# AS3364_waveform_VCA_0402_DIL_w_two_separ.net
KiCad netlist of a schematic drawn in EAGLE
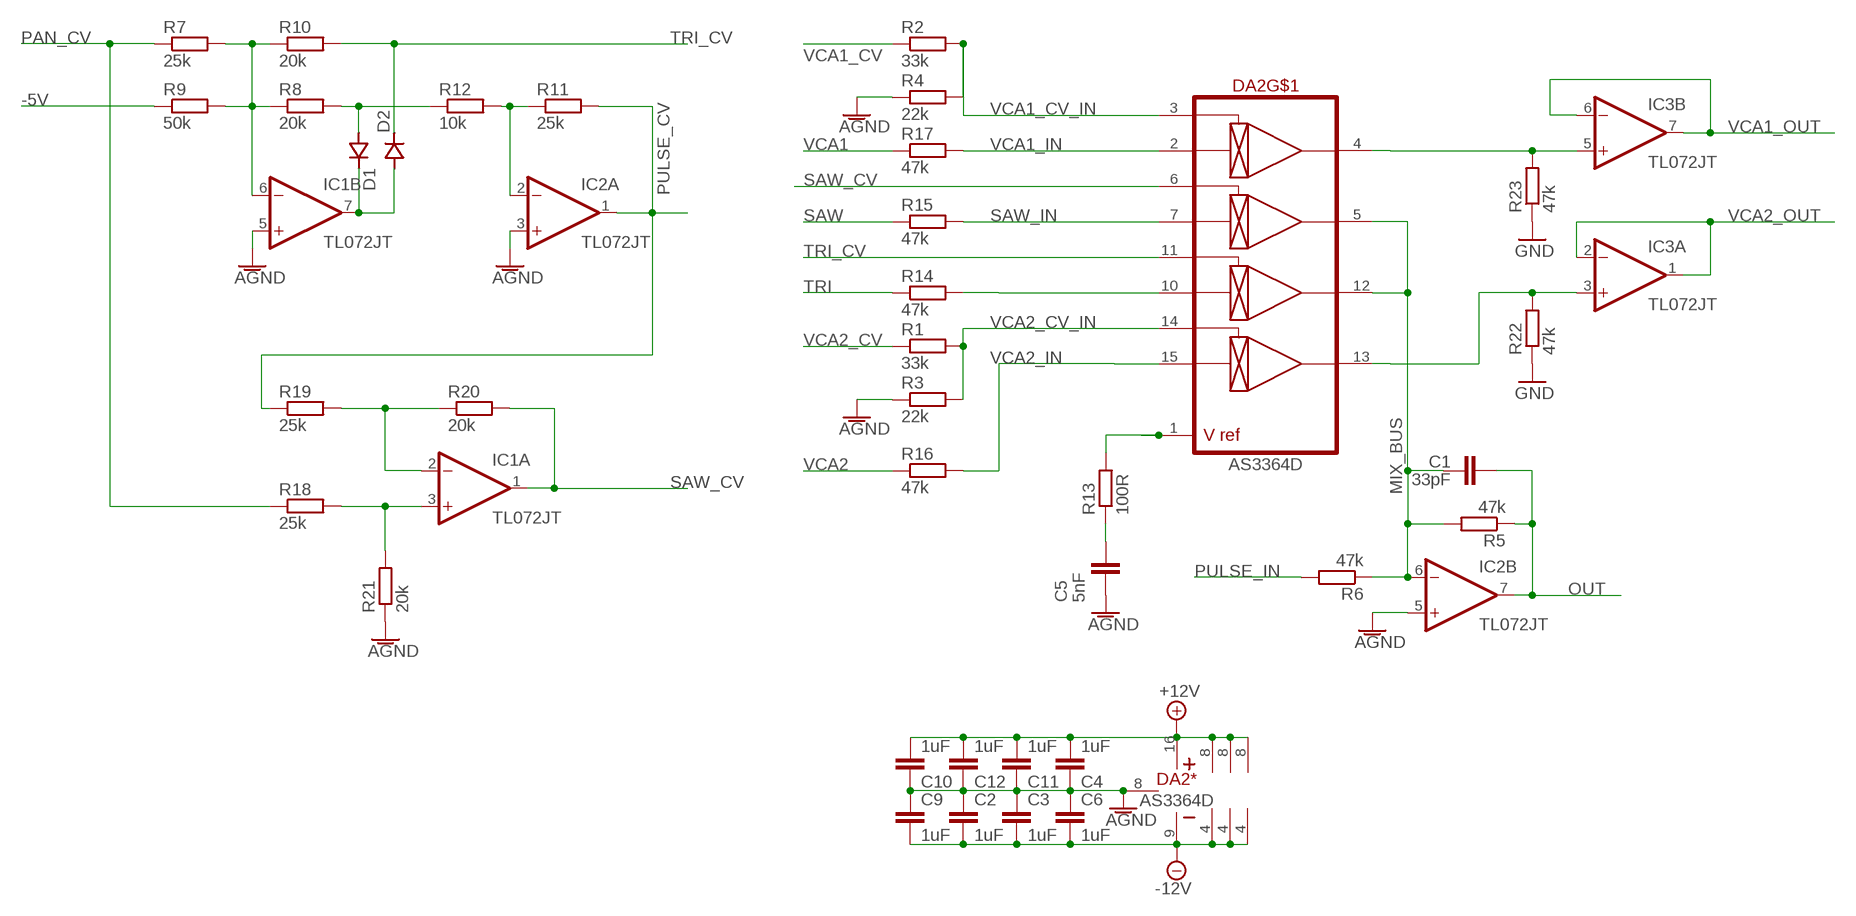
[diagram p0: schematic, sheet 1]

(export (version "E")
  (design (tool "Eeschema 10.0.6"))
  (components
    (comp (ref "C1")
      (value "33pF")
      (footprint "eagle-import:C0402-J")
      (libsource (lib "eagle-import") (part "C-EU-J"))
    )
    (comp (ref "C2")
      (value "1uF")
      (footprint "eagle-import:C0402-J")
      (libsource (lib "eagle-import") (part "C-EU-J"))
    )
    (comp (ref "C3")
      (value "1uF")
      (footprint "eagle-import:C0402-J")
      (libsource (lib "eagle-import") (part "C-EU-J"))
    )
    (comp (ref "C4")
      (value "1uF")
      (footprint "eagle-import:C0402-J")
      (libsource (lib "eagle-import") (part "C-EU-J"))
    )
    (comp (ref "C5")
      (value "5nF")
      (footprint "eagle-import:C0402-J")
      (libsource (lib "eagle-import") (part "C-EU-J"))
    )
    (comp (ref "C6")
      (value "1uF")
      (footprint "eagle-import:C0402-J")
      (libsource (lib "eagle-import") (part "C-EU-J"))
    )
    (comp (ref "C9")
      (value "1uF")
      (footprint "eagle-import:C0402-J")
      (libsource (lib "eagle-import") (part "C-EU-J"))
    )
    (comp (ref "C10")
      (value "1uF")
      (footprint "eagle-import:C0402-J")
      (libsource (lib "eagle-import") (part "C-EU-J"))
    )
    (comp (ref "C11")
      (value "1uF")
      (footprint "eagle-import:C0402-J")
      (libsource (lib "eagle-import") (part "C-EU-J"))
    )
    (comp (ref "C12")
      (value "1uF")
      (footprint "eagle-import:C0402-J")
      (libsource (lib "eagle-import") (part "C-EU-J"))
    )
    (comp (ref "D1")
      (value "DIODESOD323")
      (footprint "eagle-import:SOD323J")
      (fields (field (name "MPN") "CDSOD323-T05C"))
      (libsource (lib "eagle-import") (part "DIODESOD323"))
    )
    (comp (ref "D2")
      (value "DIODESOD323")
      (footprint "eagle-import:SOD323J")
      (fields (field (name "MPN") "CDSOD323-T05C"))
      (libsource (lib "eagle-import") (part "DIODESOD323"))
    )
    (comp (ref "DA2")
      (value "AS3364D")
      (footprint "eagle-import:DIL16J")
      (libsource (lib "eagle-import") (part "AS3364D"))
    )
    (comp (ref "IC1")
      (value "TL072JT")
      (footprint "eagle-import:TSSOP8J")
      (libsource (lib "eagle-import") (part "TL072JT"))
    )
    (comp (ref "IC2")
      (value "TL072JT")
      (footprint "eagle-import:TSSOP8J")
      (libsource (lib "eagle-import") (part "TL072JT"))
    )
    (comp (ref "IC3")
      (value "TL072JT")
      (footprint "eagle-import:TSSOP8J")
      (libsource (lib "eagle-import") (part "TL072JT"))
    )
    (comp (ref "R1")
      (value "33k")
      (footprint "eagle-import:R0402")
      (libsource (lib "eagle-import") (part "R-EU_R0402"))
    )
    (comp (ref "R2")
      (value "33k")
      (footprint "eagle-import:R0402")
      (libsource (lib "eagle-import") (part "R-EU_R0402"))
    )
    (comp (ref "R3")
      (value "22k")
      (footprint "eagle-import:R0402")
      (libsource (lib "eagle-import") (part "R-EU_R0402"))
    )
    (comp (ref "R4")
      (value "22k")
      (footprint "eagle-import:R0402")
      (libsource (lib "eagle-import") (part "R-EU_R0402"))
    )
    (comp (ref "R5")
      (value "47k")
      (footprint "eagle-import:R0402")
      (libsource (lib "eagle-import") (part "R-EU_R0402"))
    )
    (comp (ref "R6")
      (value "47k")
      (footprint "eagle-import:R0402")
      (libsource (lib "eagle-import") (part "R-EU_R0402"))
    )
    (comp (ref "R7")
      (value "25k")
      (footprint "eagle-import:R0402")
      (libsource (lib "eagle-import") (part "R-EU_R0402"))
    )
    (comp (ref "R8")
      (value "20k")
      (footprint "eagle-import:R0402")
      (libsource (lib "eagle-import") (part "R-EU_R0402"))
    )
    (comp (ref "R9")
      (value "50k")
      (footprint "eagle-import:R0402")
      (libsource (lib "eagle-import") (part "R-EU_R0402"))
    )
    (comp (ref "R10")
      (value "20k")
      (footprint "eagle-import:R0402")
      (libsource (lib "eagle-import") (part "R-EU_R0402"))
    )
    (comp (ref "R11")
      (value "25k")
      (footprint "eagle-import:R0402")
      (libsource (lib "eagle-import") (part "R-EU_R0402"))
    )
    (comp (ref "R12")
      (value "10k")
      (footprint "eagle-import:R0402")
      (libsource (lib "eagle-import") (part "R-EU_R0402"))
    )
    (comp (ref "R13")
      (value "100R")
      (footprint "eagle-import:R0402")
      (libsource (lib "eagle-import") (part "R-EU_R0402"))
    )
    (comp (ref "R14")
      (value "47k")
      (footprint "eagle-import:R0402")
      (libsource (lib "eagle-import") (part "R-EU_R0402"))
    )
    (comp (ref "R15")
      (value "47k")
      (footprint "eagle-import:R0402")
      (libsource (lib "eagle-import") (part "R-EU_R0402"))
    )
    (comp (ref "R16")
      (value "47k")
      (footprint "eagle-import:R0402")
      (libsource (lib "eagle-import") (part "R-EU_R0402"))
    )
    (comp (ref "R17")
      (value "47k")
      (footprint "eagle-import:R0402")
      (libsource (lib "eagle-import") (part "R-EU_R0402"))
    )
    (comp (ref "R18")
      (value "25k")
      (footprint "eagle-import:R0402")
      (libsource (lib "eagle-import") (part "R-EU_R0402"))
    )
    (comp (ref "R19")
      (value "25k")
      (footprint "eagle-import:R0402")
      (libsource (lib "eagle-import") (part "R-EU_R0402"))
    )
    (comp (ref "R20")
      (value "20k")
      (footprint "eagle-import:R0402")
      (libsource (lib "eagle-import") (part "R-EU_R0402"))
    )
    (comp (ref "R21")
      (value "20k")
      (footprint "eagle-import:R0402")
      (libsource (lib "eagle-import") (part "R-EU_R0402"))
    )
    (comp (ref "R22")
      (value "47k")
      (footprint "eagle-import:R0402")
      (libsource (lib "eagle-import") (part "R-EU_R0402"))
    )
    (comp (ref "R23")
      (value "47k")
      (footprint "eagle-import:R0402")
      (libsource (lib "eagle-import") (part "R-EU_R0402"))
    )
  )
  (nets
    (net (code "1") (name "+12V") (class "Default")
      (node (ref "C10") (pin "2") (pinfunction "2_2") (pintype "passive"))
      (node (ref "C11") (pin "2") (pinfunction "2_2") (pintype "passive"))
      (node (ref "C12") (pin "2") (pinfunction "2_2") (pintype "passive"))
      (node (ref "C4") (pin "2") (pinfunction "2_2") (pintype "passive"))
      (node (ref "DA2") (pin "16") (pinfunction "V+_16") (pintype "power_in"))
      (node (ref "IC1") (pin "8") (pinfunction "V+_8") (pintype "power_in"))
      (node (ref "IC2") (pin "8") (pinfunction "V+_8") (pintype "power_in"))
      (node (ref "IC3") (pin "8") (pinfunction "V+_8") (pintype "power_in"))
    )
    (net (code "2") (name "-12V") (class "Default")
      (node (ref "C2") (pin "1") (pinfunction "1_1") (pintype "passive"))
      (node (ref "C3") (pin "1") (pinfunction "1_1") (pintype "passive"))
      (node (ref "C6") (pin "1") (pinfunction "1_1") (pintype "passive"))
      (node (ref "C9") (pin "1") (pinfunction "1_1") (pintype "passive"))
      (node (ref "DA2") (pin "9") (pinfunction "V-_9") (pintype "power_in"))
      (node (ref "IC1") (pin "4") (pinfunction "V-_4") (pintype "power_in"))
      (node (ref "IC2") (pin "4") (pinfunction "V-_4") (pintype "power_in"))
      (node (ref "IC3") (pin "4") (pinfunction "V-_4") (pintype "power_in"))
    )
    (net (code "3") (name "/-5V") (class "Default")
      (node (ref "R9") (pin "1") (pinfunction "1_1") (pintype "passive"))
    )
    (net (code "4") (name "/MIX_BUS") (class "Default")
      (node (ref "C1") (pin "2") (pinfunction "2_2") (pintype "passive"))
      (node (ref "DA2") (pin "12") (pinfunction "OUT3_12") (pintype "output"))
      (node (ref "DA2") (pin "5") (pinfunction "OUT2_5") (pintype "output"))
      (node (ref "IC2") (pin "6") (pinfunction "-IN_6") (pintype "input"))
      (node (ref "R5") (pin "2") (pinfunction "2_2") (pintype "passive"))
      (node (ref "R6") (pin "1") (pinfunction "1_1") (pintype "passive"))
    )
    (net (code "5") (name "/OUT") (class "Default")
      (node (ref "C1") (pin "1") (pinfunction "1_1") (pintype "passive"))
      (node (ref "IC2") (pin "7") (pinfunction "OUT_7") (pintype "output"))
      (node (ref "R5") (pin "1") (pinfunction "1_1") (pintype "passive"))
    )
    (net (code "6") (name "/PAN_CV") (class "Default")
      (node (ref "R18") (pin "1") (pinfunction "1_1") (pintype "passive"))
      (node (ref "R7") (pin "1") (pinfunction "1_1") (pintype "passive"))
    )
    (net (code "7") (name "/PULSE_CV") (class "Default")
      (node (ref "IC2") (pin "1") (pinfunction "OUT_1") (pintype "output"))
      (node (ref "R11") (pin "2") (pinfunction "2_2") (pintype "passive"))
      (node (ref "R19") (pin "1") (pinfunction "1_1") (pintype "passive"))
    )
    (net (code "8") (name "/PULSE_IN") (class "Default")
      (node (ref "R6") (pin "2") (pinfunction "2_2") (pintype "passive"))
    )
    (net (code "9") (name "/SAW") (class "Default")
      (node (ref "R15") (pin "1") (pinfunction "1_1") (pintype "passive"))
    )
    (net (code "10") (name "/SAW_CV") (class "Default")
      (node (ref "DA2") (pin "6") (pinfunction "CV2_6") (pintype "input"))
      (node (ref "IC1") (pin "1") (pinfunction "OUT_1") (pintype "output"))
      (node (ref "R20") (pin "2") (pinfunction "2_2") (pintype "passive"))
    )
    (net (code "11") (name "/SAW_IN") (class "Default")
      (node (ref "DA2") (pin "7") (pinfunction "IN2_7") (pintype "input"))
      (node (ref "R15") (pin "2") (pinfunction "2_2") (pintype "passive"))
    )
    (net (code "12") (name "/TRI") (class "Default")
      (node (ref "R14") (pin "1") (pinfunction "1_1") (pintype "passive"))
    )
    (net (code "13") (name "/TRI_CV") (class "Default")
      (node (ref "D2") (pin "1") (pinfunction "C_1") (pintype "passive"))
      (node (ref "DA2") (pin "11") (pinfunction "CV3_11") (pintype "input"))
      (node (ref "R10") (pin "2") (pinfunction "2_2") (pintype "passive"))
    )
    (net (code "14") (name "/VCA1") (class "Default")
      (node (ref "R17") (pin "1") (pinfunction "1_1") (pintype "passive"))
    )
    (net (code "15") (name "/VCA1_CV") (class "Default")
      (node (ref "R2") (pin "1") (pinfunction "1_1") (pintype "passive"))
    )
    (net (code "16") (name "/VCA1_CV_IN") (class "Default")
      (node (ref "DA2") (pin "3") (pinfunction "CV1_3") (pintype "input"))
      (node (ref "R2") (pin "2") (pinfunction "2_2") (pintype "passive"))
      (node (ref "R4") (pin "2") (pinfunction "2_2") (pintype "passive"))
    )
    (net (code "17") (name "/VCA1_IN") (class "Default")
      (node (ref "DA2") (pin "2") (pinfunction "IN1_2") (pintype "input"))
      (node (ref "R17") (pin "2") (pinfunction "2_2") (pintype "passive"))
    )
    (net (code "18") (name "/VCA1_OUT") (class "Default")
      (node (ref "IC3") (pin "6") (pinfunction "-IN_6") (pintype "input"))
      (node (ref "IC3") (pin "7") (pinfunction "OUT_7") (pintype "output"))
    )
    (net (code "19") (name "/VCA2") (class "Default")
      (node (ref "R16") (pin "1") (pinfunction "1_1") (pintype "passive"))
    )
    (net (code "20") (name "/VCA2_CV") (class "Default")
      (node (ref "R1") (pin "1") (pinfunction "1_1") (pintype "passive"))
    )
    (net (code "21") (name "/VCA2_CV_IN") (class "Default")
      (node (ref "DA2") (pin "14") (pinfunction "CV4_14") (pintype "input"))
      (node (ref "R1") (pin "2") (pinfunction "2_2") (pintype "passive"))
      (node (ref "R3") (pin "2") (pinfunction "2_2") (pintype "passive"))
    )
    (net (code "22") (name "/VCA2_IN") (class "Default")
      (node (ref "DA2") (pin "15") (pinfunction "IN4_15") (pintype "input"))
      (node (ref "R16") (pin "2") (pinfunction "2_2") (pintype "passive"))
    )
    (net (code "23") (name "/VCA2_OUT") (class "Default")
      (node (ref "IC3") (pin "1") (pinfunction "OUT_1") (pintype "output"))
      (node (ref "IC3") (pin "2") (pinfunction "-IN_2") (pintype "input"))
    )
    (net (code "24") (name "AGND") (class "Default")
      (node (ref "C10") (pin "1") (pinfunction "1_1") (pintype "passive"))
      (node (ref "C11") (pin "1") (pinfunction "1_1") (pintype "passive"))
      (node (ref "C12") (pin "1") (pinfunction "1_1") (pintype "passive"))
      (node (ref "C2") (pin "2") (pinfunction "2_2") (pintype "passive"))
      (node (ref "C3") (pin "2") (pinfunction "2_2") (pintype "passive"))
      (node (ref "C4") (pin "1") (pinfunction "1_1") (pintype "passive"))
      (node (ref "C5") (pin "1") (pinfunction "1_1") (pintype "passive"))
      (node (ref "C6") (pin "2") (pinfunction "2_2") (pintype "passive"))
      (node (ref "C9") (pin "2") (pinfunction "2_2") (pintype "passive"))
      (node (ref "DA2") (pin "8") (pinfunction "GND_8") (pintype "power_in"))
      (node (ref "IC1") (pin "5") (pinfunction "+IN_5") (pintype "input"))
      (node (ref "IC2") (pin "3") (pinfunction "+IN_3") (pintype "input"))
      (node (ref "IC2") (pin "5") (pinfunction "+IN_5") (pintype "input"))
      (node (ref "R21") (pin "1") (pinfunction "1_1") (pintype "passive"))
      (node (ref "R3") (pin "1") (pinfunction "1_1") (pintype "passive"))
      (node (ref "R4") (pin "1") (pinfunction "1_1") (pintype "passive"))
    )
    (net (code "25") (name "GND") (class "Default")
      (node (ref "R22") (pin "1") (pinfunction "1_1") (pintype "passive"))
      (node (ref "R23") (pin "1") (pinfunction "1_1") (pintype "passive"))
    )
    (net (code "26") (name "Net-(C5-Pad2)") (class "Default")
      (node (ref "C5") (pin "2") (pinfunction "2_2") (pintype "passive"))
      (node (ref "R13") (pin "1") (pinfunction "1_1") (pintype "passive"))
    )
    (net (code "27") (name "Net-(D1-A)") (class "Default")
      (node (ref "D1") (pin "2") (pinfunction "A_2") (pintype "passive"))
      (node (ref "R12") (pin "1") (pinfunction "1_1") (pintype "passive"))
      (node (ref "R8") (pin "2") (pinfunction "2_2") (pintype "passive"))
    )
    (net (code "28") (name "Net-(D1-C)") (class "Default")
      (node (ref "D1") (pin "1") (pinfunction "C_1") (pintype "passive"))
      (node (ref "D2") (pin "2") (pinfunction "A_2") (pintype "passive"))
      (node (ref "IC1") (pin "7") (pinfunction "OUT_7") (pintype "output"))
    )
    (net (code "29") (name "Net-(DA2B-IN3)") (class "Default")
      (node (ref "DA2") (pin "10") (pinfunction "IN3_10") (pintype "input"))
      (node (ref "R14") (pin "2") (pinfunction "2_2") (pintype "passive"))
    )
    (net (code "30") (name "Net-(DA2B-OUT1)") (class "Default")
      (node (ref "DA2") (pin "4") (pinfunction "OUT1_4") (pintype "output"))
      (node (ref "IC3") (pin "5") (pinfunction "+IN_5") (pintype "input"))
      (node (ref "R23") (pin "2") (pinfunction "2_2") (pintype "passive"))
    )
    (net (code "31") (name "Net-(DA2B-OUT4)") (class "Default")
      (node (ref "DA2") (pin "13") (pinfunction "OUT4_13") (pintype "output"))
      (node (ref "IC3") (pin "3") (pinfunction "+IN_3") (pintype "input"))
      (node (ref "R22") (pin "2") (pinfunction "2_2") (pintype "passive"))
    )
    (net (code "32") (name "Net-(DA2B-VREF)") (class "Default")
      (node (ref "DA2") (pin "1") (pinfunction "VREF_1") (pintype "output"))
      (node (ref "R13") (pin "2") (pinfunction "2_2") (pintype "passive"))
    )
    (net (code "33") (name "Net-(IC1A-+IN)") (class "Default")
      (node (ref "IC1") (pin "3") (pinfunction "+IN_3") (pintype "input"))
      (node (ref "R18") (pin "2") (pinfunction "2_2") (pintype "passive"))
      (node (ref "R21") (pin "2") (pinfunction "2_2") (pintype "passive"))
    )
    (net (code "34") (name "Net-(IC1A--IN)") (class "Default")
      (node (ref "IC1") (pin "2") (pinfunction "-IN_2") (pintype "input"))
      (node (ref "R19") (pin "2") (pinfunction "2_2") (pintype "passive"))
      (node (ref "R20") (pin "1") (pinfunction "1_1") (pintype "passive"))
    )
    (net (code "35") (name "Net-(IC1B--IN)") (class "Default")
      (node (ref "IC1") (pin "6") (pinfunction "-IN_6") (pintype "input"))
      (node (ref "R10") (pin "1") (pinfunction "1_1") (pintype "passive"))
      (node (ref "R7") (pin "2") (pinfunction "2_2") (pintype "passive"))
      (node (ref "R8") (pin "1") (pinfunction "1_1") (pintype "passive"))
      (node (ref "R9") (pin "2") (pinfunction "2_2") (pintype "passive"))
    )
    (net (code "36") (name "Net-(IC2A--IN)") (class "Default")
      (node (ref "IC2") (pin "2") (pinfunction "-IN_2") (pintype "input"))
      (node (ref "R11") (pin "1") (pinfunction "1_1") (pintype "passive"))
      (node (ref "R12") (pin "2") (pinfunction "2_2") (pintype "passive"))
    )
  )
)
